# Microcontroller.net
KiCad netlist of a schematic drawn in Altium Designer
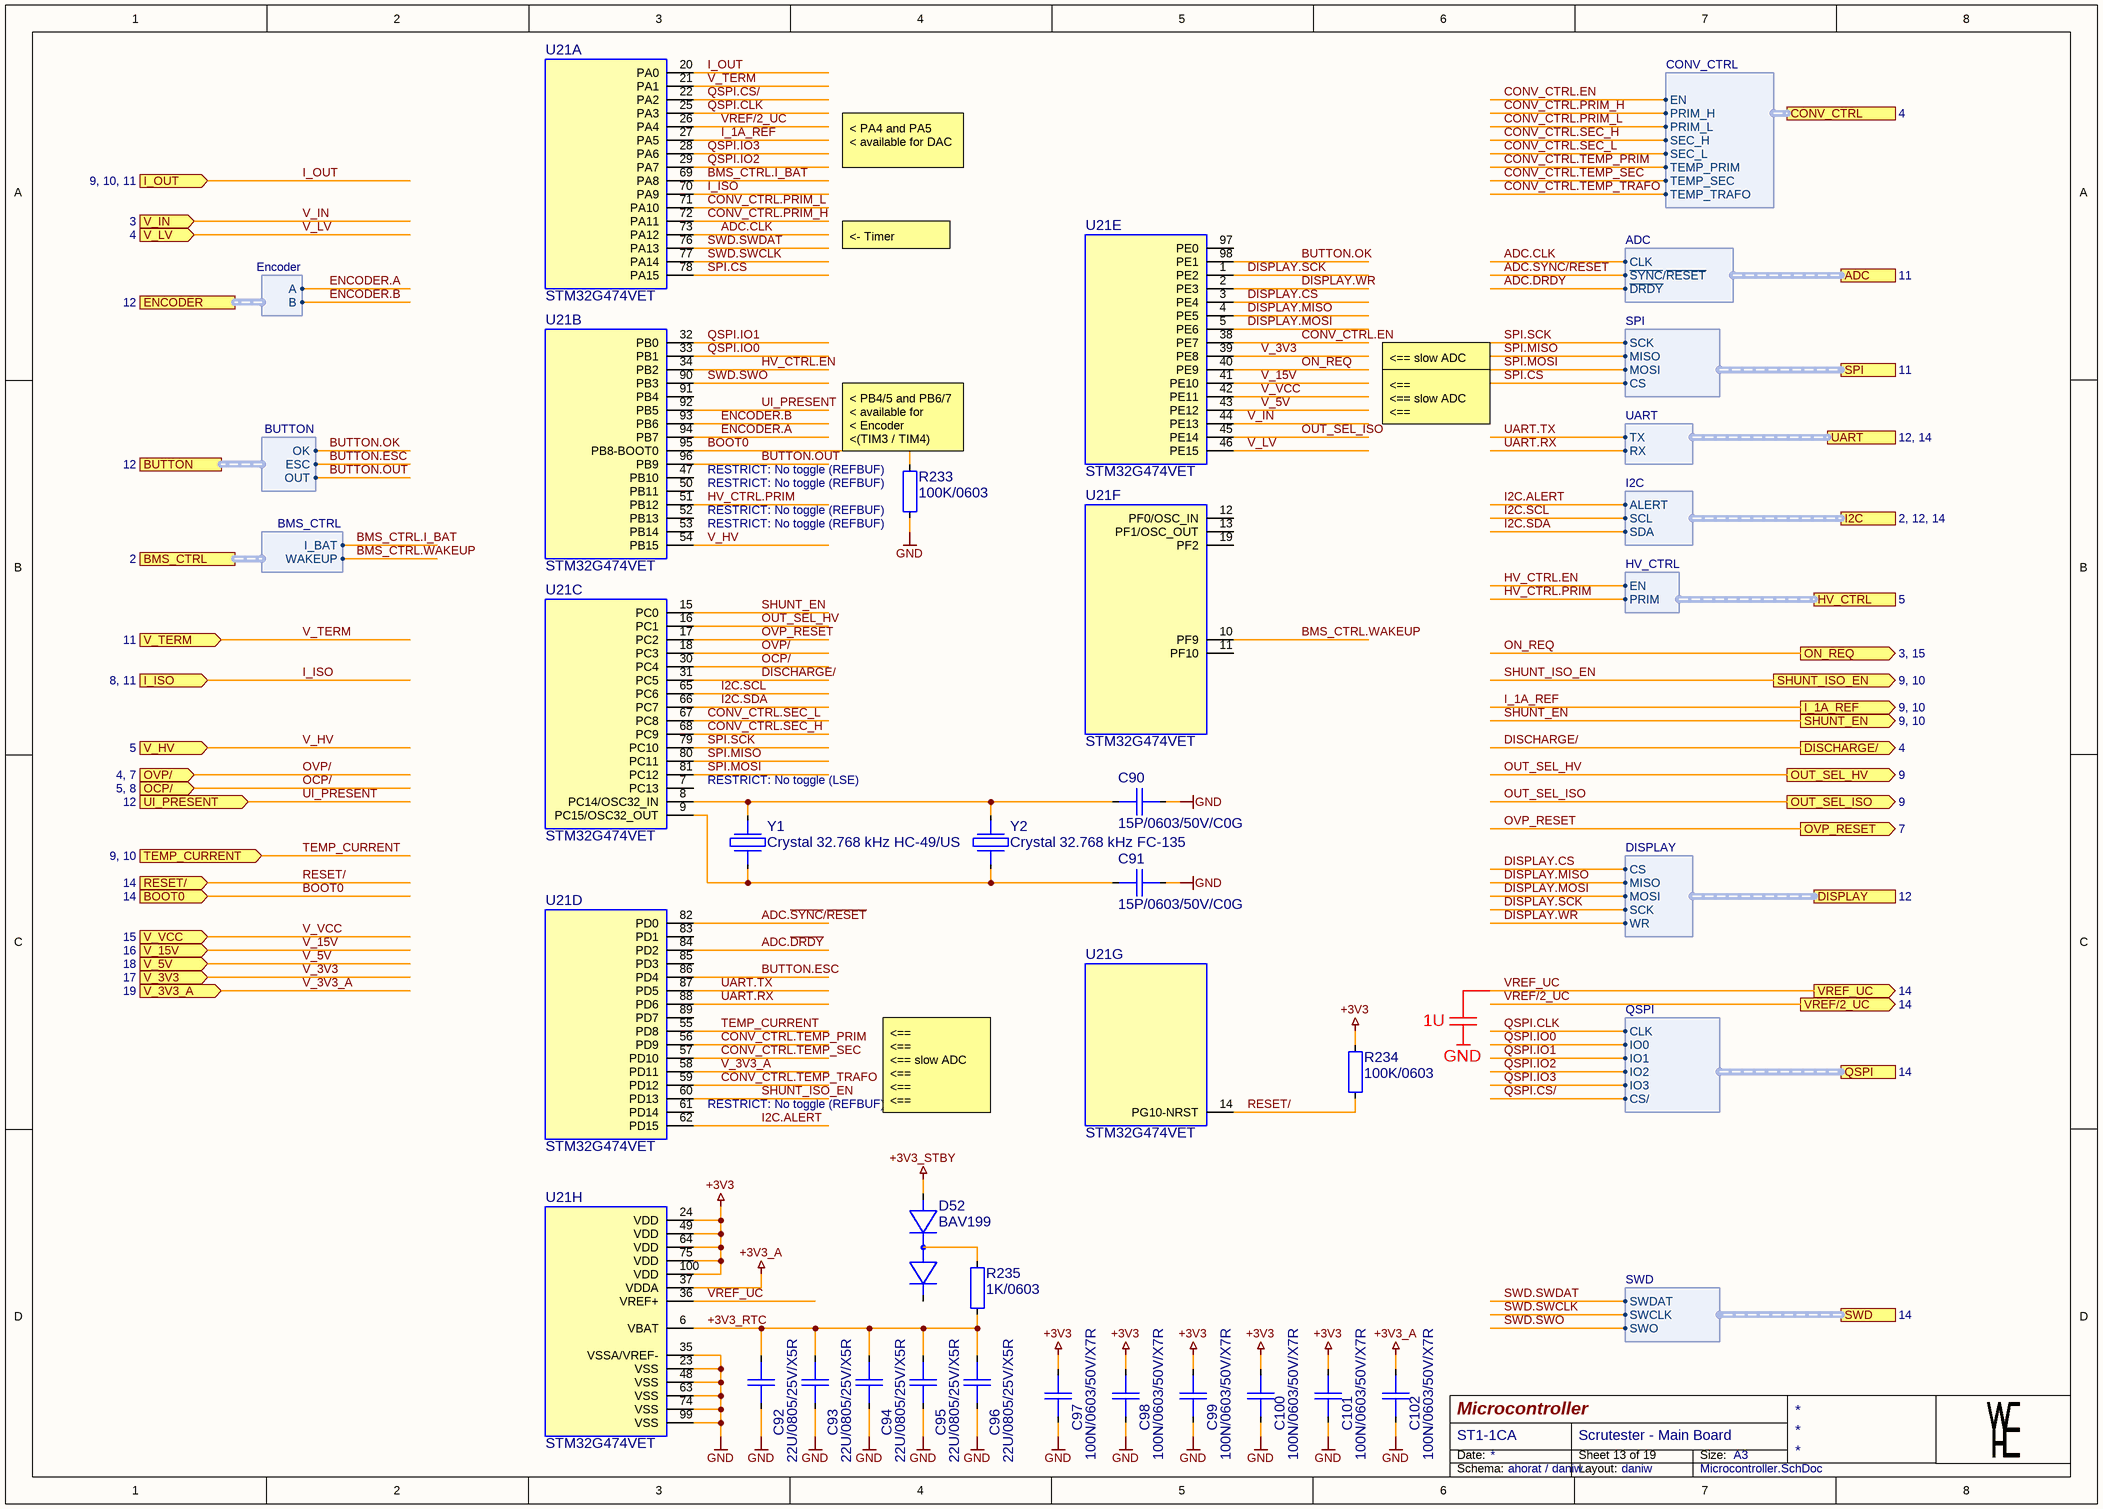
[diagram p0: Microcontroller.SchDoc]

(export (version "E")
  (design (tool "Eeschema 10.0.6"))
  (components
    (comp (ref "C90")
      (value "15P/0603/50V/C0G")
      (footprint "CAP0603_C0G")
      (description "CAP SM 0603 15pF 50V C0G")
      (fields (field (name "MANUFACTURER") "GENERIC"))
      (libsource (lib "daniw_altium_lib") (part "C"))
    )
    (comp (ref "C91")
      (value "15P/0603/50V/C0G")
      (footprint "CAP0603_C0G")
      (description "CAP SM 0603 15pF 50V C0G")
      (fields (field (name "MANUFACTURER") "GENERIC"))
      (libsource (lib "daniw_altium_lib") (part "C"))
    )
    (comp (ref "C92")
      (value "22U/0805/25V/X5R")
      (footprint "CAP0805_X7R")
      (description "CAP SM 0805 22uF 25V X5R")
      (fields (field (name "MANUFACTURER") "GENERIC"))
      (libsource (lib "daniw_altium_lib") (part "C"))
    )
    (comp (ref "C93")
      (value "22U/0805/25V/X5R")
      (footprint "CAP0805_X7R")
      (description "CAP SM 0805 22uF 25V X5R")
      (fields (field (name "MANUFACTURER") "GENERIC"))
      (libsource (lib "daniw_altium_lib") (part "C"))
    )
    (comp (ref "C94")
      (value "22U/0805/25V/X5R")
      (footprint "CAP0805_X7R")
      (description "CAP SM 0805 22uF 25V X5R")
      (fields (field (name "MANUFACTURER") "GENERIC"))
      (libsource (lib "daniw_altium_lib") (part "C"))
    )
    (comp (ref "C95")
      (value "22U/0805/25V/X5R")
      (footprint "CAP0805_X7R")
      (description "CAP SM 0805 22uF 25V X5R")
      (fields (field (name "MANUFACTURER") "GENERIC"))
      (libsource (lib "daniw_altium_lib") (part "C"))
    )
    (comp (ref "C96")
      (value "22U/0805/25V/X5R")
      (footprint "CAP0805_X7R")
      (description "CAP SM 0805 22uF 25V X5R")
      (fields (field (name "MANUFACTURER") "GENERIC"))
      (libsource (lib "daniw_altium_lib") (part "C"))
    )
    (comp (ref "C97")
      (value "100N/0603/50V/X7R")
      (footprint "CAP0603_X7R")
      (description "CAP SM 0603 100nF 50V X7R")
      (fields (field (name "MANUFACTURER") "GENERIC"))
      (libsource (lib "daniw_altium_lib") (part "C"))
    )
    (comp (ref "C98")
      (value "100N/0603/50V/X7R")
      (footprint "CAP0603_X7R")
      (description "CAP SM 0603 100nF 50V X7R")
      (fields (field (name "MANUFACTURER") "GENERIC"))
      (libsource (lib "daniw_altium_lib") (part "C"))
    )
    (comp (ref "C99")
      (value "100N/0603/50V/X7R")
      (footprint "CAP0603_X7R")
      (description "CAP SM 0603 100nF 50V X7R")
      (fields (field (name "MANUFACTURER") "GENERIC"))
      (libsource (lib "daniw_altium_lib") (part "C"))
    )
    (comp (ref "C100")
      (value "100N/0603/50V/X7R")
      (footprint "CAP0603_X7R")
      (description "CAP SM 0603 100nF 50V X7R")
      (fields (field (name "MANUFACTURER") "GENERIC"))
      (libsource (lib "daniw_altium_lib") (part "C"))
    )
    (comp (ref "C101")
      (value "100N/0603/50V/X7R")
      (footprint "CAP0603_X7R")
      (description "CAP SM 0603 100nF 50V X7R")
      (fields (field (name "MANUFACTURER") "GENERIC"))
      (libsource (lib "daniw_altium_lib") (part "C"))
    )
    (comp (ref "C102")
      (value "100N/0603/50V/X7R")
      (footprint "CAP0603_X7R")
      (description "CAP SM 0603 100nF 50V X7R")
      (fields (field (name "MANUFACTURER") "GENERIC"))
      (libsource (lib "daniw_altium_lib") (part "C"))
    )
    (comp (ref "D52")
      (value "BAV199")
      (footprint "SOT2395P280X125-3-SE")
      (description "Silicon Low Leakage Diode 85V")
      (fields (field (name "MANUFACTURER") "Infineon Technologies"))
      (libsource (lib "daniw_altium_lib") (part "D_Serie"))
    )
    (comp (ref "R233")
      (value "100K/0603")
      (footprint "R0603-0.40-WW")
      (description "RES SM 0603 100K")
      (fields (field (name "MANUFACTURER") "GENERIC"))
      (libsource (lib "daniw_altium_lib") (part "R"))
    )
    (comp (ref "R234")
      (value "100K/0603")
      (footprint "R0603-0.40-WW")
      (description "RES SM 0603 100K")
      (fields (field (name "MANUFACTURER") "GENERIC"))
      (libsource (lib "daniw_altium_lib") (part "R"))
    )
    (comp (ref "R235")
      (value "1K/0603")
      (footprint "R0603-0.40-WW")
      (description "RES SM 0603 1K")
      (fields (field (name "MANUFACTURER") "GENERIC"))
      (libsource (lib "daniw_altium_lib") (part "R"))
    )
    (comp (ref "U21")
      (value "STM32G474VET")
      (footprint "QFP050P1600X1600X160-100")
      (fields (field (name "MANUFACTURER") "ST Microelectronics"))
      (libsource (lib "daniw_altium_lib") (part "STM32G474 QFP-100"))
    )
    (comp (ref "Y1")
      (value "Crystal 32.768 kHz HC-49/US")
      (footprint "CYSMD275P760X320C230")
      (description "32.768 kHz ±20ppm Crystal 12,5pF HC-49/US")
      (fields (field (name "MANUFACTURER") "CJKJ"))
      (libsource (lib "daniw_altium_lib") (part "Crystal"))
    )
    (comp (ref "Y2")
      (value "Crystal 32.768 kHz FC-135")
      (footprint "CYSMD250P320X150X090")
      (description "32.768 kHz ±20ppm Crystal 12,5pF FC-135")
      (fields (field (name "MANUFACTURER") "Epson"))
      (libsource (lib "daniw_altium_lib") (part "Crystal"))
    )
  )
  (nets
    (net (code "13") (name "+3V3") (class "Default")
      (node (ref "C100") (pin "1") (pinfunction "1_1") (pintype "passive"))
      (node (ref "C101") (pin "1") (pinfunction "1_1") (pintype "passive"))
      (node (ref "C97") (pin "1") (pinfunction "1_1") (pintype "passive"))
      (node (ref "C98") (pin "1") (pinfunction "1_1") (pintype "passive"))
      (node (ref "C99") (pin "1") (pinfunction "1_1") (pintype "passive"))
      (node (ref "R234") (pin "1") (pinfunction "1_1") (pintype "passive"))
      (node (ref "U21") (pin "100") (pinfunction "VDD_100") (pintype "passive"))
      (node (ref "U21") (pin "24") (pinfunction "VDD_24") (pintype "passive"))
      (node (ref "U21") (pin "49") (pinfunction "VDD_49") (pintype "passive"))
      (node (ref "U21") (pin "64") (pinfunction "VDD_64") (pintype "passive"))
      (node (ref "U21") (pin "75") (pinfunction "VDD_75") (pintype "passive"))
    )
    (net (code "14") (name "+3V3_A") (class "Default")
      (node (ref "C102") (pin "1") (pinfunction "1_1") (pintype "passive"))
      (node (ref "U21") (pin "37") (pinfunction "VDDA_37") (pintype "passive"))
    )
    (net (code "15") (name "+3V3_STBY") (class "Default")
      (node (ref "D52") (pin "1") (pinfunction "A1_1") (pintype "passive"))
    )
    (net (code "16") (name "/+3V3_RTC") (class "Default")
      (node (ref "C92") (pin "1") (pinfunction "1_1") (pintype "passive"))
      (node (ref "C93") (pin "1") (pinfunction "1_1") (pintype "passive"))
      (node (ref "C94") (pin "1") (pinfunction "1_1") (pintype "passive"))
      (node (ref "C95") (pin "1") (pinfunction "1_1") (pintype "passive"))
      (node (ref "C96") (pin "1") (pinfunction "1_1") (pintype "passive"))
      (node (ref "R235") (pin "2") (pinfunction "2_2") (pintype "passive"))
      (node (ref "U21") (pin "6") (pinfunction "VBAT_6") (pintype "passive"))
    )
    (net (code "17") (name "/ADC.CLK") (class "Default")
      (node (ref "U21") (pin "73") (pinfunction "PA12_73") (pintype "passive"))
    )
    (net (code "18") (name "/ADC.~{DRDY}") (class "Default")
      (node (ref "U21") (pin "84") (pinfunction "PD2_84") (pintype "passive"))
    )
    (net (code "19") (name "/ADC.~{SYNC}{slash}~{RESET}") (class "Default")
      (node (ref "U21") (pin "82") (pinfunction "PD0_82") (pintype "passive"))
    )
    (net (code "20") (name "/BMS_CTRL.I_BAT") (class "Default")
      (node (ref "U21") (pin "69") (pinfunction "PA8_69") (pintype "passive"))
    )
    (net (code "21") (name "/BMS_CTRL.WAKEUP") (class "Default")
      (node (ref "U21") (pin "10") (pinfunction "PF9_10") (pintype "passive"))
    )
    (net (code "22") (name "/BOOT0") (class "Default")
      (node (ref "R233") (pin "1") (pinfunction "1_1") (pintype "passive"))
      (node (ref "U21") (pin "95") (pinfunction "PB8-BOOT0_95") (pintype "passive"))
    )
    (net (code "23") (name "/BUTTON.ESC") (class "Default")
      (node (ref "U21") (pin "86") (pinfunction "PD4_86") (pintype "passive"))
    )
    (net (code "24") (name "/BUTTON.OK") (class "Default")
      (node (ref "U21") (pin "98") (pinfunction "PE1_98") (pintype "passive"))
    )
    (net (code "25") (name "/BUTTON.OUT") (class "Default")
      (node (ref "U21") (pin "96") (pinfunction "PB9_96") (pintype "passive"))
    )
    (net (code "26") (name "/CONV_CTRL.EN") (class "Default")
      (node (ref "U21") (pin "38") (pinfunction "PE7_38") (pintype "passive"))
    )
    (net (code "27") (name "/CONV_CTRL.PRIM_H") (class "Default")
      (node (ref "U21") (pin "72") (pinfunction "PA11_72") (pintype "passive"))
    )
    (net (code "28") (name "/CONV_CTRL.PRIM_L") (class "Default")
      (node (ref "U21") (pin "71") (pinfunction "PA10_71") (pintype "passive"))
    )
    (net (code "29") (name "/CONV_CTRL.SEC_H") (class "Default")
      (node (ref "U21") (pin "68") (pinfunction "PC9_68") (pintype "passive"))
    )
    (net (code "30") (name "/CONV_CTRL.SEC_L") (class "Default")
      (node (ref "U21") (pin "67") (pinfunction "PC8_67") (pintype "passive"))
    )
    (net (code "31") (name "/CONV_CTRL.TEMP_PRIM") (class "Default")
      (node (ref "U21") (pin "56") (pinfunction "PD9_56") (pintype "passive"))
    )
    (net (code "32") (name "/CONV_CTRL.TEMP_SEC") (class "Default")
      (node (ref "U21") (pin "57") (pinfunction "PD10_57") (pintype "passive"))
    )
    (net (code "33") (name "/CONV_CTRL.TEMP_TRAFO") (class "Default")
      (node (ref "U21") (pin "59") (pinfunction "PD12_59") (pintype "passive"))
    )
    (net (code "34") (name "/DISCHARGE{slash}") (class "Default")
      (node (ref "U21") (pin "31") (pinfunction "PC5_31") (pintype "passive"))
    )
    (net (code "35") (name "/DISPLAY.CS") (class "Default")
      (node (ref "U21") (pin "3") (pinfunction "PE4_3") (pintype "passive"))
    )
    (net (code "36") (name "/DISPLAY.MISO") (class "Default")
      (node (ref "U21") (pin "4") (pinfunction "PE5_4") (pintype "passive"))
    )
    (net (code "37") (name "/DISPLAY.MOSI") (class "Default")
      (node (ref "U21") (pin "5") (pinfunction "PE6_5") (pintype "passive"))
    )
    (net (code "38") (name "/DISPLAY.SCK") (class "Default")
      (node (ref "U21") (pin "1") (pinfunction "PE2_1") (pintype "passive"))
    )
    (net (code "39") (name "/DISPLAY.WR") (class "Default")
      (node (ref "U21") (pin "2") (pinfunction "PE3_2") (pintype "passive"))
    )
    (net (code "40") (name "/ENCODER.A") (class "Default")
      (node (ref "U21") (pin "94") (pinfunction "PB7_94") (pintype "passive"))
    )
    (net (code "41") (name "/ENCODER.B") (class "Default")
      (node (ref "U21") (pin "93") (pinfunction "PB6_93") (pintype "passive"))
    )
    (net (code "42") (name "/HV_CTRL.EN") (class "Default")
      (node (ref "U21") (pin "34") (pinfunction "PB2_34") (pintype "passive"))
    )
    (net (code "43") (name "/HV_CTRL.PRIM") (class "Default")
      (node (ref "U21") (pin "51") (pinfunction "PB12_51") (pintype "passive"))
    )
    (net (code "44") (name "/I2C.ALERT") (class "Default")
      (node (ref "U21") (pin "62") (pinfunction "PD15_62") (pintype "passive"))
    )
    (net (code "45") (name "/I2C.SCL") (class "Default")
      (node (ref "U21") (pin "65") (pinfunction "PC6_65") (pintype "passive"))
    )
    (net (code "46") (name "/I2C.SDA") (class "Default")
      (node (ref "U21") (pin "66") (pinfunction "PC7_66") (pintype "passive"))
    )
    (net (code "47") (name "/I_1A_REF") (class "Default")
      (node (ref "U21") (pin "27") (pinfunction "PA5_27") (pintype "passive"))
    )
    (net (code "48") (name "/I_ISO") (class "Default")
      (node (ref "U21") (pin "70") (pinfunction "PA9_70") (pintype "passive"))
    )
    (net (code "49") (name "/I_OUT") (class "Default")
      (node (ref "U21") (pin "20") (pinfunction "PA0_20") (pintype "passive"))
    )
    (net (code "50") (name "/OCP{slash}") (class "Default")
      (node (ref "U21") (pin "30") (pinfunction "PC4_30") (pintype "passive"))
    )
    (net (code "51") (name "/ON_REQ") (class "Default")
      (node (ref "U21") (pin "40") (pinfunction "PE9_40") (pintype "passive"))
    )
    (net (code "52") (name "/OUT_SEL_HV") (class "Default")
      (node (ref "U21") (pin "16") (pinfunction "PC1_16") (pintype "passive"))
    )
    (net (code "53") (name "/OUT_SEL_ISO") (class "Default")
      (node (ref "U21") (pin "45") (pinfunction "PE14_45") (pintype "passive"))
    )
    (net (code "54") (name "/OVP_RESET") (class "Default")
      (node (ref "U21") (pin "17") (pinfunction "PC2_17") (pintype "passive"))
    )
    (net (code "55") (name "/OVP{slash}") (class "Default")
      (node (ref "U21") (pin "18") (pinfunction "PC3_18") (pintype "passive"))
    )
    (net (code "56") (name "/QSPI.CLK") (class "Default")
      (node (ref "U21") (pin "25") (pinfunction "PA3_25") (pintype "passive"))
    )
    (net (code "57") (name "/QSPI.CS{slash}") (class "Default")
      (node (ref "U21") (pin "22") (pinfunction "PA2_22") (pintype "passive"))
    )
    (net (code "58") (name "/QSPI.IO0") (class "Default")
      (node (ref "U21") (pin "33") (pinfunction "PB1_33") (pintype "passive"))
    )
    (net (code "59") (name "/QSPI.IO1") (class "Default")
      (node (ref "U21") (pin "32") (pinfunction "PB0_32") (pintype "passive"))
    )
    (net (code "60") (name "/QSPI.IO2") (class "Default")
      (node (ref "U21") (pin "29") (pinfunction "PA7_29") (pintype "passive"))
    )
    (net (code "61") (name "/QSPI.IO3") (class "Default")
      (node (ref "U21") (pin "28") (pinfunction "PA6_28") (pintype "passive"))
    )
    (net (code "62") (name "/RESET{slash}") (class "Default")
      (node (ref "R234") (pin "2") (pinfunction "2_2") (pintype "passive"))
      (node (ref "U21") (pin "14") (pinfunction "PG10-NRST_14") (pintype "passive"))
    )
    (net (code "63") (name "/SHUNT_EN") (class "Default")
      (node (ref "U21") (pin "15") (pinfunction "PC0_15") (pintype "passive"))
    )
    (net (code "64") (name "/SHUNT_ISO_EN") (class "Default")
      (node (ref "U21") (pin "60") (pinfunction "PD13_60") (pintype "passive"))
    )
    (net (code "65") (name "/SPI.CS") (class "Default")
      (node (ref "U21") (pin "78") (pinfunction "PA15_78") (pintype "passive"))
    )
    (net (code "66") (name "/SPI.MISO") (class "Default")
      (node (ref "U21") (pin "80") (pinfunction "PC11_80") (pintype "passive"))
    )
    (net (code "67") (name "/SPI.MOSI") (class "Default")
      (node (ref "U21") (pin "81") (pinfunction "PC12_81") (pintype "passive"))
    )
    (net (code "68") (name "/SPI.SCK") (class "Default")
      (node (ref "U21") (pin "79") (pinfunction "PC10_79") (pintype "passive"))
    )
    (net (code "69") (name "/SWD.SWCLK") (class "Default")
      (node (ref "U21") (pin "77") (pinfunction "PA14_77") (pintype "passive"))
    )
    (net (code "70") (name "/SWD.SWDAT") (class "Default")
      (node (ref "U21") (pin "76") (pinfunction "PA13_76") (pintype "passive"))
    )
    (net (code "71") (name "/SWD.SWO") (class "Default")
      (node (ref "U21") (pin "90") (pinfunction "PB3_90") (pintype "passive"))
    )
    (net (code "72") (name "/TEMP_CURRENT") (class "Default")
      (node (ref "U21") (pin "55") (pinfunction "PD8_55") (pintype "passive"))
    )
    (net (code "73") (name "/UART.RX") (class "Default")
      (node (ref "U21") (pin "88") (pinfunction "PD6_88") (pintype "passive"))
    )
    (net (code "74") (name "/UART.TX") (class "Default")
      (node (ref "U21") (pin "87") (pinfunction "PD5_87") (pintype "passive"))
    )
    (net (code "75") (name "/UI_PRESENT") (class "Default")
      (node (ref "U21") (pin "92") (pinfunction "PB5_92") (pintype "passive"))
    )
    (net (code "76") (name "/VREF_UC") (class "Default")
      (node (ref "U21") (pin "36") (pinfunction "VREF+_36") (pintype "passive"))
    )
    (net (code "77") (name "/VREF{slash}2_UC") (class "Default")
      (node (ref "U21") (pin "26") (pinfunction "PA4_26") (pintype "passive"))
    )
    (net (code "78") (name "/V_3V3") (class "Default")
      (node (ref "U21") (pin "39") (pinfunction "PE8_39") (pintype "passive"))
    )
    (net (code "79") (name "/V_3V3_A") (class "Default")
      (node (ref "U21") (pin "58") (pinfunction "PD11_58") (pintype "passive"))
    )
    (net (code "80") (name "/V_5V") (class "Default")
      (node (ref "U21") (pin "43") (pinfunction "PE12_43") (pintype "passive"))
    )
    (net (code "81") (name "/V_15V") (class "Default")
      (node (ref "U21") (pin "41") (pinfunction "PE10_41") (pintype "passive"))
    )
    (net (code "82") (name "/V_HV") (class "Default")
      (node (ref "U21") (pin "54") (pinfunction "PB15_54") (pintype "passive"))
    )
    (net (code "83") (name "/V_IN") (class "Default")
      (node (ref "U21") (pin "44") (pinfunction "PE13_44") (pintype "passive"))
    )
    (net (code "84") (name "/V_LV") (class "Default")
      (node (ref "U21") (pin "46") (pinfunction "PE15_46") (pintype "passive"))
    )
    (net (code "85") (name "/V_TERM") (class "Default")
      (node (ref "U21") (pin "21") (pinfunction "PA1_21") (pintype "passive"))
    )
    (net (code "86") (name "/V_VCC") (class "Default")
      (node (ref "U21") (pin "42") (pinfunction "PE11_42") (pintype "passive"))
    )
    (net (code "99") (name "GND") (class "Default")
      (node (ref "C100") (pin "2") (pinfunction "2_2") (pintype "passive"))
      (node (ref "C101") (pin "2") (pinfunction "2_2") (pintype "passive"))
      (node (ref "C102") (pin "2") (pinfunction "2_2") (pintype "passive"))
      (node (ref "C90") (pin "2") (pinfunction "2_2") (pintype "passive"))
      (node (ref "C91") (pin "2") (pinfunction "2_2") (pintype "passive"))
      (node (ref "C92") (pin "2") (pinfunction "2_2") (pintype "passive"))
      (node (ref "C93") (pin "2") (pinfunction "2_2") (pintype "passive"))
      (node (ref "C94") (pin "2") (pinfunction "2_2") (pintype "passive"))
      (node (ref "C95") (pin "2") (pinfunction "2_2") (pintype "passive"))
      (node (ref "C96") (pin "2") (pinfunction "2_2") (pintype "passive"))
      (node (ref "C97") (pin "2") (pinfunction "2_2") (pintype "passive"))
      (node (ref "C98") (pin "2") (pinfunction "2_2") (pintype "passive"))
      (node (ref "C99") (pin "2") (pinfunction "2_2") (pintype "passive"))
      (node (ref "R233") (pin "2") (pinfunction "2_2") (pintype "passive"))
      (node (ref "U21") (pin "23") (pinfunction "VSS_23") (pintype "passive"))
      (node (ref "U21") (pin "35") (pinfunction "VSSA/VREF-_35") (pintype "passive"))
      (node (ref "U21") (pin "48") (pinfunction "VSS_48") (pintype "passive"))
      (node (ref "U21") (pin "63") (pinfunction "VSS_63") (pintype "passive"))
      (node (ref "U21") (pin "74") (pinfunction "VSS_74") (pintype "passive"))
      (node (ref "U21") (pin "99") (pinfunction "VSS_99") (pintype "passive"))
    )
    (net (code "100") (name "Net-(D52-K1{slash}A2)") (class "Default")
      (node (ref "D52") (pin "3") (pinfunction "K1/A2_3") (pintype "passive"))
      (node (ref "R235") (pin "1") (pinfunction "1_1") (pintype "passive"))
    )
    (net (code "101") (name "Net-(U21C-PC14{slash}OSC32_IN)") (class "Default")
      (node (ref "C90") (pin "1") (pinfunction "1_1") (pintype "passive"))
      (node (ref "U21") (pin "8") (pinfunction "PC14/OSC32_IN_8") (pintype "passive"))
      (node (ref "Y1") (pin "1") (pinfunction "1_1") (pintype "passive"))
      (node (ref "Y2") (pin "1") (pinfunction "1_1") (pintype "passive"))
    )
    (net (code "102") (name "Net-(U21C-PC15{slash}OSC32_OUT)") (class "Default")
      (node (ref "C91") (pin "1") (pinfunction "1_1") (pintype "passive"))
      (node (ref "U21") (pin "9") (pinfunction "PC15/OSC32_OUT_9") (pintype "passive"))
      (node (ref "Y1") (pin "2") (pinfunction "2_2") (pintype "passive"))
      (node (ref "Y2") (pin "2") (pinfunction "2_2") (pintype "passive"))
    )
    (net (code "103") (name "unconnected-(D52-K2-Pad2)") (class "Default")
      (node (ref "D52") (pin "2") (pinfunction "K2_2") (pintype "passive"))
    )
    (net (code "104") (name "unconnected-(U21B-PB4-Pad91)") (class "Default")
      (node (ref "U21") (pin "91") (pinfunction "PB4_91") (pintype "passive"))
    )
    (net (code "105") (name "unconnected-(U21B-PB10-Pad47)") (class "Default")
      (node (ref "U21") (pin "47") (pinfunction "PB10_47") (pintype "passive"))
    )
    (net (code "106") (name "unconnected-(U21B-PB11-Pad50)") (class "Default")
      (node (ref "U21") (pin "50") (pinfunction "PB11_50") (pintype "passive"))
    )
    (net (code "107") (name "unconnected-(U21B-PB13-Pad52)") (class "Default")
      (node (ref "U21") (pin "52") (pinfunction "PB13_52") (pintype "passive"))
    )
    (net (code "108") (name "unconnected-(U21B-PB14-Pad53)") (class "Default")
      (node (ref "U21") (pin "53") (pinfunction "PB14_53") (pintype "passive"))
    )
    (net (code "109") (name "unconnected-(U21C-PC13-Pad7)") (class "Default")
      (node (ref "U21") (pin "7") (pinfunction "PC13_7") (pintype "passive"))
    )
    (net (code "110") (name "unconnected-(U21D-PD1-Pad83)") (class "Default")
      (node (ref "U21") (pin "83") (pinfunction "PD1_83") (pintype "passive"))
    )
    (net (code "111") (name "unconnected-(U21D-PD3-Pad85)") (class "Default")
      (node (ref "U21") (pin "85") (pinfunction "PD3_85") (pintype "passive"))
    )
    (net (code "112") (name "unconnected-(U21D-PD7-Pad89)") (class "Default")
      (node (ref "U21") (pin "89") (pinfunction "PD7_89") (pintype "passive"))
    )
    (net (code "113") (name "unconnected-(U21D-PD14-Pad61)") (class "Default")
      (node (ref "U21") (pin "61") (pinfunction "PD14_61") (pintype "passive"))
    )
    (net (code "114") (name "unconnected-(U21E-PE0-Pad97)") (class "Default")
      (node (ref "U21") (pin "97") (pinfunction "PE0_97") (pintype "passive"))
    )
    (net (code "115") (name "unconnected-(U21F-PF0{slash}OSC_IN-Pad12)") (class "Default")
      (node (ref "U21") (pin "12") (pinfunction "PF0/OSC_IN_12") (pintype "passive"))
    )
    (net (code "116") (name "unconnected-(U21F-PF1{slash}OSC_OUT-Pad13)") (class "Default")
      (node (ref "U21") (pin "13") (pinfunction "PF1/OSC_OUT_13") (pintype "passive"))
    )
    (net (code "117") (name "unconnected-(U21F-PF2-Pad19)") (class "Default")
      (node (ref "U21") (pin "19") (pinfunction "PF2_19") (pintype "passive"))
    )
    (net (code "118") (name "unconnected-(U21F-PF10-Pad11)") (class "Default")
      (node (ref "U21") (pin "11") (pinfunction "PF10_11") (pintype "passive"))
    )
  )
)
